# EarButton.net
KiCad netlist of a schematic drawn in EAGLE
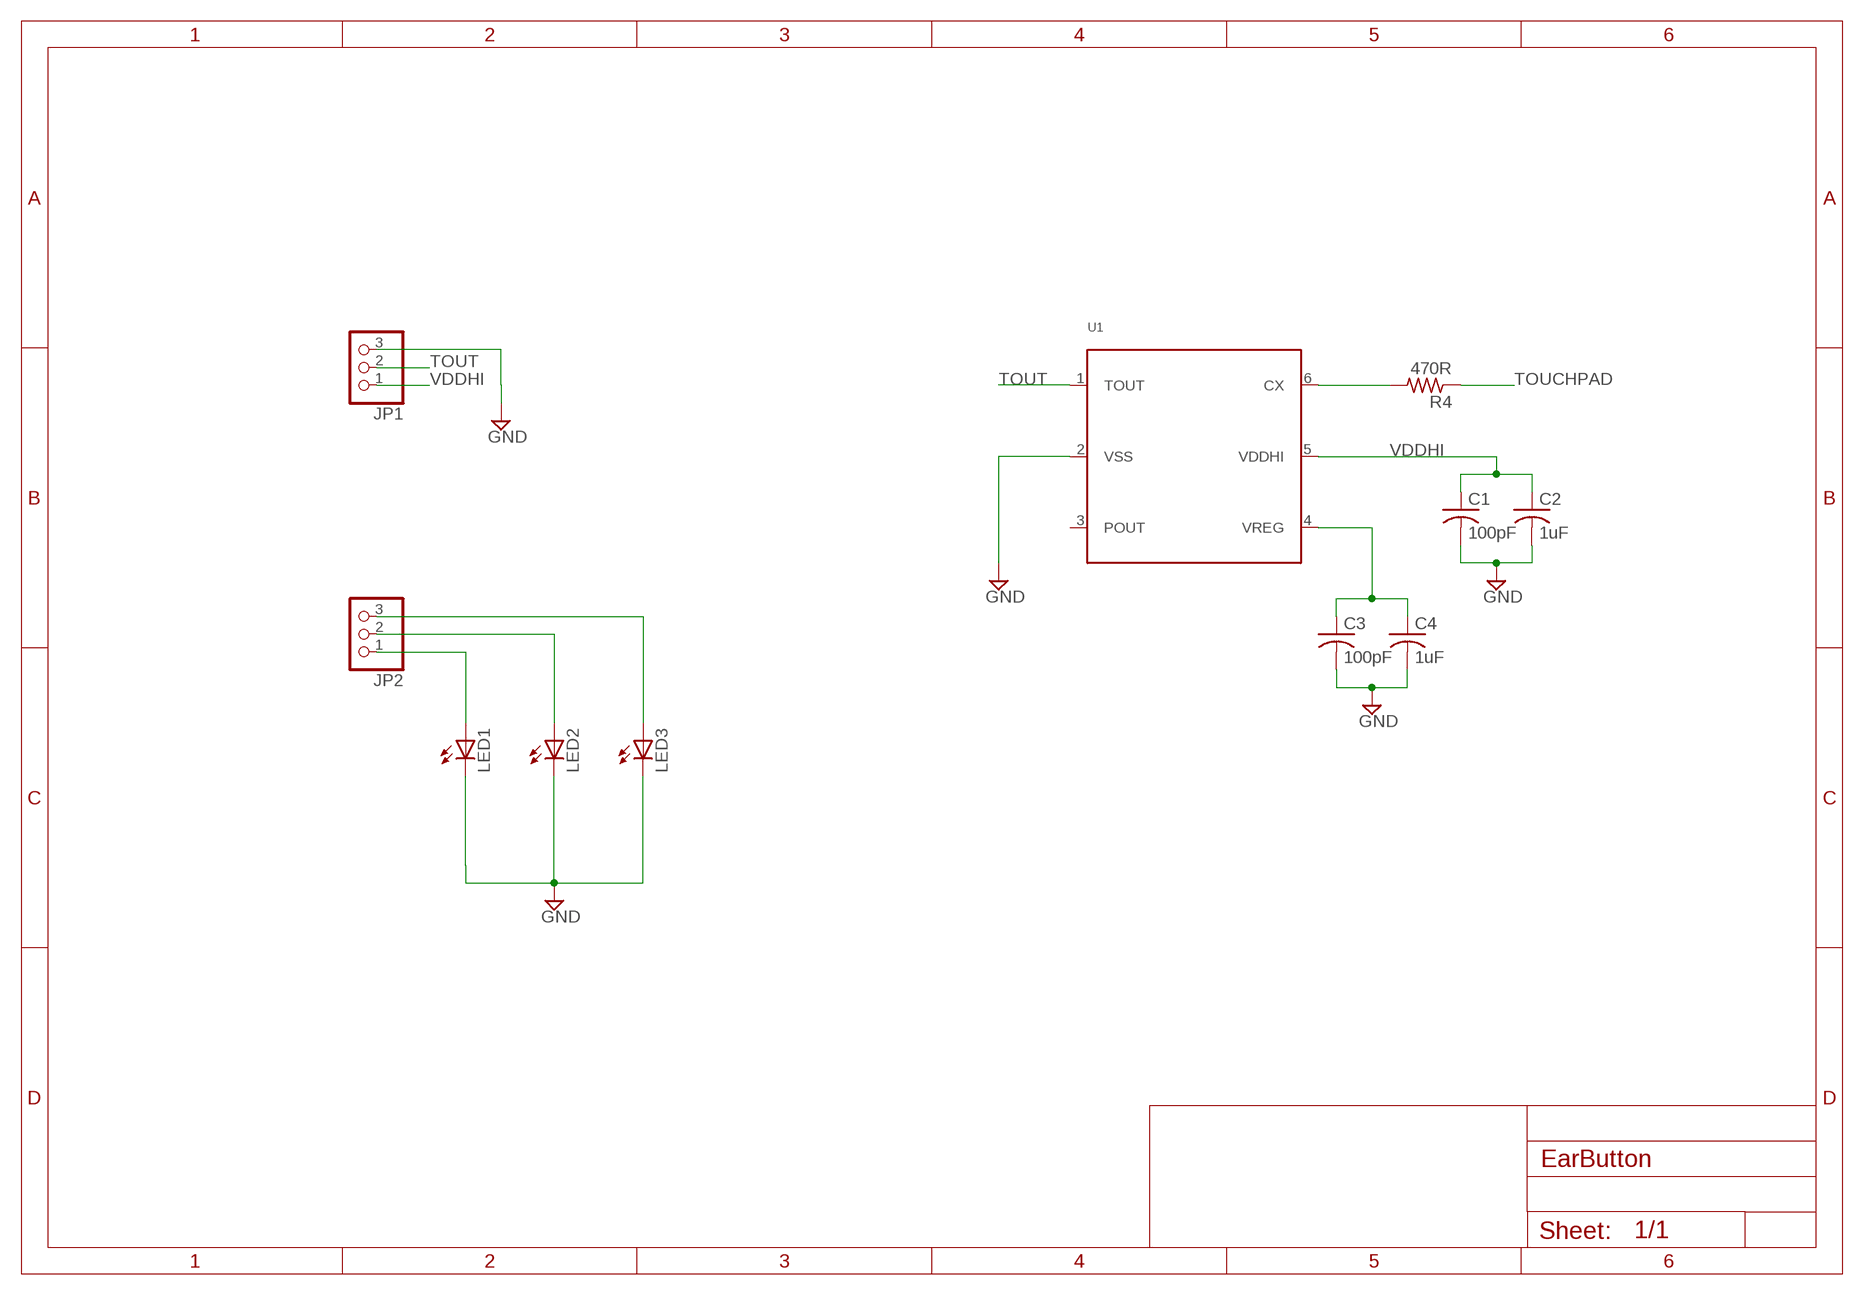
[diagram p0: schematic, sheet 1]

(export (version "E")
  (design (tool "Eeschema 10.0.6"))
  (components
    (comp (ref "C1")
      (value "100pF")
      (footprint "eagle-import:C0603K")
      (libsource (lib "eagle-import") (part "C-USC0603K"))
    )
    (comp (ref "C2")
      (value "1uF")
      (footprint "eagle-import:C0603K")
      (libsource (lib "eagle-import") (part "C-USC0603K"))
    )
    (comp (ref "C3")
      (value "100pF")
      (footprint "eagle-import:C0603K")
      (libsource (lib "eagle-import") (part "C-USC0603K"))
    )
    (comp (ref "C4")
      (value "1uF")
      (footprint "eagle-import:C0603K")
      (libsource (lib "eagle-import") (part "C-USC0603K"))
    )
    (comp (ref "JP1")
      (value "PINHD-1X3")
      (footprint "eagle-import:1X03")
      (libsource (lib "eagle-import") (part "PINHD-1X3"))
    )
    (comp (ref "JP2")
      (value "PINHD-1X3")
      (footprint "eagle-import:1X03")
      (libsource (lib "eagle-import") (part "PINHD-1X3"))
    )
    (comp (ref "LED1")
      (value "LEDCHIPLED_1206")
      (footprint "eagle-import:CHIPLED_1206")
      (libsource (lib "eagle-import") (part "LEDCHIPLED_1206"))
    )
    (comp (ref "LED2")
      (value "LEDCHIPLED_1206")
      (footprint "eagle-import:CHIPLED_1206")
      (libsource (lib "eagle-import") (part "LEDCHIPLED_1206"))
    )
    (comp (ref "LED3")
      (value "LEDCHIPLED_1206")
      (footprint "eagle-import:CHIPLED_1206")
      (libsource (lib "eagle-import") (part "LEDCHIPLED_1206"))
    )
    (comp (ref "R4")
      (value "470R")
      (footprint "eagle-import:R0603")
      (libsource (lib "eagle-import") (part "R-US_R0603"))
    )
    (comp (ref "U1")
      (value "IQS127")
      (footprint "eagle-import:SOT23-6")
      (libsource (lib "eagle-import") (part "IQS127"))
    )
  )
  (nets
    (net (code "1") (name "/TOUCHPAD") (class "Default")
      (node (ref "R4") (pin "1") (pinfunction "1_1") (pintype "passive"))
    )
    (net (code "2") (name "/TOUT") (class "Default")
      (node (ref "JP1") (pin "2") (pinfunction "2_2") (pintype "passive"))
      (node (ref "U1") (pin "1") (pinfunction "TOUT_1") (pintype "output"))
    )
    (net (code "3") (name "/VDDHI") (class "Default")
      (node (ref "C1") (pin "1") (pinfunction "1_1") (pintype "passive"))
      (node (ref "C2") (pin "1") (pinfunction "1_1") (pintype "passive"))
      (node (ref "JP1") (pin "1") (pinfunction "1_1") (pintype "passive"))
      (node (ref "U1") (pin "5") (pinfunction "VDDHI_5") (pintype "power_in"))
    )
    (net (code "4") (name "GND") (class "Default")
      (node (ref "C1") (pin "2") (pinfunction "2_2") (pintype "passive"))
      (node (ref "C2") (pin "2") (pinfunction "2_2") (pintype "passive"))
      (node (ref "C3") (pin "2") (pinfunction "2_2") (pintype "passive"))
      (node (ref "C4") (pin "2") (pinfunction "2_2") (pintype "passive"))
      (node (ref "JP1") (pin "3") (pinfunction "3_3") (pintype "passive"))
      (node (ref "LED1") (pin "C") (pinfunction "C_C") (pintype "passive"))
      (node (ref "LED2") (pin "C") (pinfunction "C_C") (pintype "passive"))
      (node (ref "LED3") (pin "C") (pinfunction "C_C") (pintype "passive"))
      (node (ref "U1") (pin "2") (pinfunction "VSS_2") (pintype "power_in"))
    )
    (net (code "5") (name "Net-(JP2-Pad1)") (class "Default")
      (node (ref "JP2") (pin "1") (pinfunction "1_1") (pintype "passive"))
      (node (ref "LED1") (pin "A") (pinfunction "A_A") (pintype "passive"))
    )
    (net (code "6") (name "Net-(JP2-Pad2)") (class "Default")
      (node (ref "JP2") (pin "2") (pinfunction "2_2") (pintype "passive"))
      (node (ref "LED2") (pin "A") (pinfunction "A_A") (pintype "passive"))
    )
    (net (code "7") (name "Net-(JP2-Pad3)") (class "Default")
      (node (ref "JP2") (pin "3") (pinfunction "3_3") (pintype "passive"))
      (node (ref "LED3") (pin "A") (pinfunction "A_A") (pintype "passive"))
    )
    (net (code "8") (name "Net-(U1-CX)") (class "Default")
      (node (ref "R4") (pin "2") (pinfunction "2_2") (pintype "passive"))
      (node (ref "U1") (pin "6") (pinfunction "CX_6") (pintype "bidirectional"))
    )
    (net (code "9") (name "Net-(U1-VREG)") (class "Default")
      (node (ref "C3") (pin "1") (pinfunction "1_1") (pintype "passive"))
      (node (ref "C4") (pin "1") (pinfunction "1_1") (pintype "passive"))
      (node (ref "U1") (pin "4") (pinfunction "VREG_4") (pintype "bidirectional"))
    )
    (net (code "10") (name "unconnected-(U1-POUT-Pad3)") (class "Default")
      (node (ref "U1") (pin "3") (pinfunction "POUT_3") (pintype "output"))
    )
  )
)
